# CVTOP.net
KiCad netlist of a schematic drawn in Altium Designer
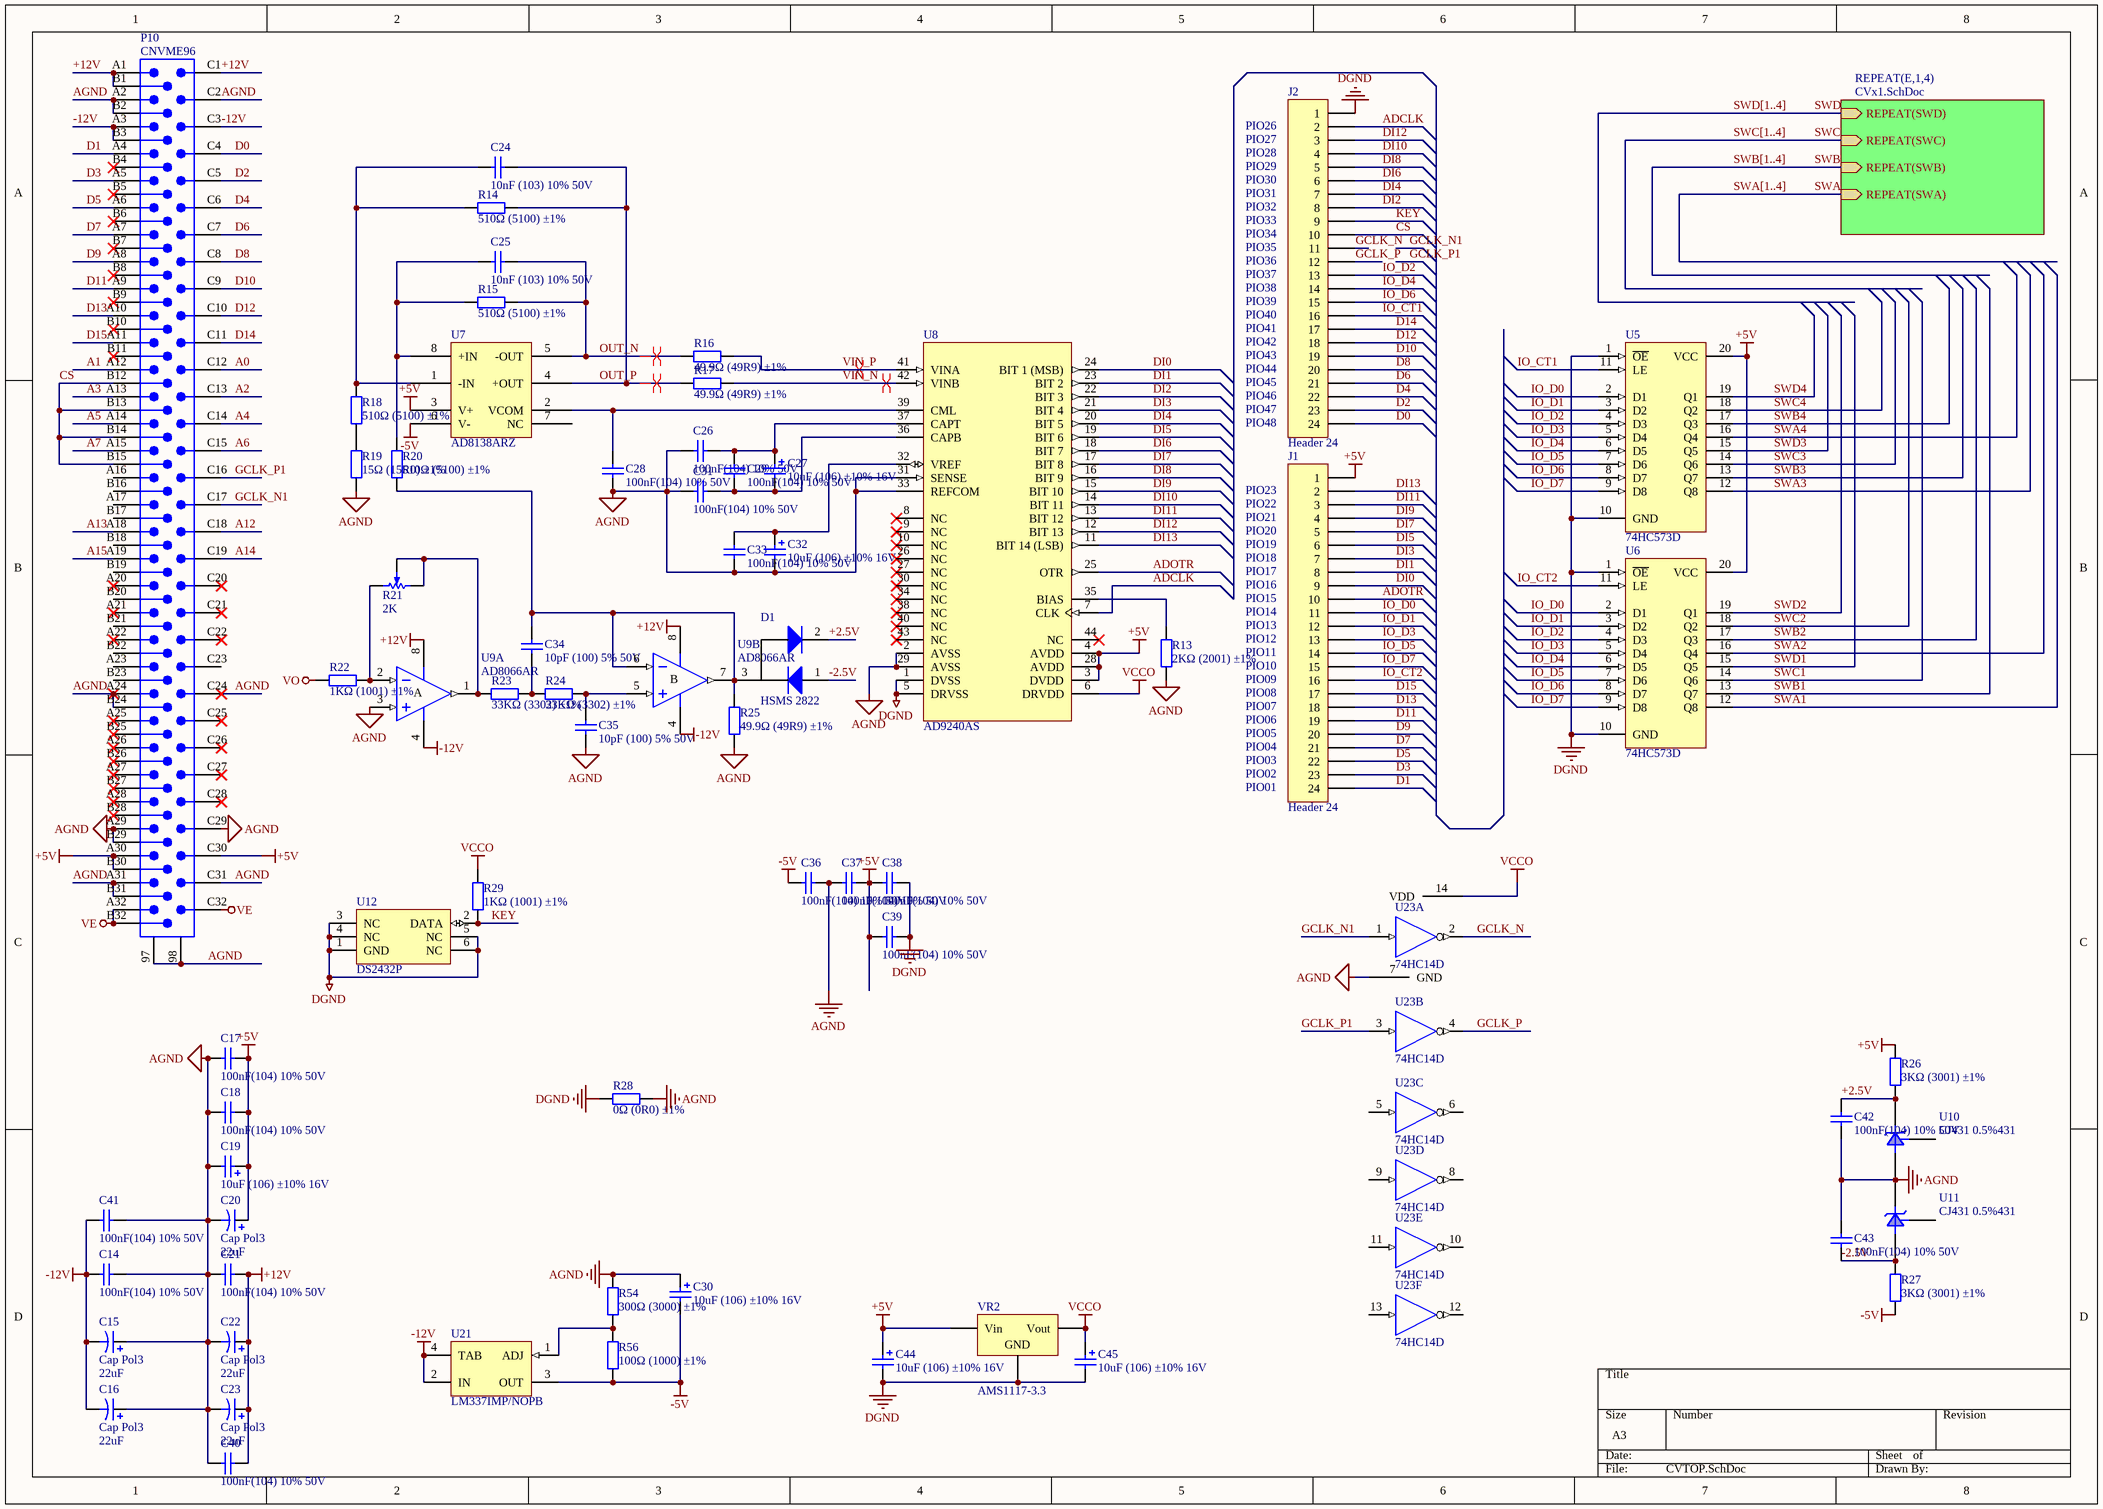
[diagram p0: CVTOP.SchDoc]

(export (version "E")
  (design (tool "Eeschema 10.0.6"))
  (components
    (comp (ref "C14")
      (value "100nF(104) 10% 50V")
      (footprint "LC-0805_C")
      (description "贴片电容")
      (libsource (lib "Miscellaneous Devices LC") (part "0805 100nF(104) 10% 50V"))
    )
    (comp (ref "C15")
      (value "Cap Pol3")
      (footprint "C2225")
      (description "Polarized Capacitor (Surface Mount)")
      (fields (field (name "ALTIUM_VALUE") "22uF") (field (name "PUBLISHER") "Altium Limited"))
      (libsource (lib "Miscellaneous Devices") (part "Cap Pol3"))
    )
    (comp (ref "C16")
      (value "Cap Pol3")
      (footprint "C2225")
      (description "Polarized Capacitor (Surface Mount)")
      (fields (field (name "ALTIUM_VALUE") "22uF") (field (name "PUBLISHER") "Altium Limited"))
      (libsource (lib "Miscellaneous Devices") (part "Cap Pol3"))
    )
    (comp (ref "C17")
      (value "100nF(104) 10% 50V")
      (footprint "LC-0805_C")
      (description "贴片电容")
      (libsource (lib "Miscellaneous Devices LC") (part "0805 100nF(104) 10% 50V"))
    )
    (comp (ref "C18")
      (value "100nF(104) 10% 50V")
      (footprint "LC-0805_C")
      (description "贴片电容")
      (libsource (lib "Miscellaneous Devices LC") (part "0805 100nF(104) 10% 50V"))
    )
    (comp (ref "C19")
      (value "10uF (106) ±10% 16V")
      (footprint "LC-CASE-A_3216")
      (description "钽电容")
      (libsource (lib "Miscellaneous Devices LC") (part "3216 10uF (106) 10% 16V"))
    )
    (comp (ref "C20")
      (value "Cap Pol3")
      (footprint "C2225")
      (description "Polarized Capacitor (Surface Mount)")
      (fields (field (name "ALTIUM_VALUE") "22uF") (field (name "PUBLISHER") "Altium Limited"))
      (libsource (lib "Miscellaneous Devices") (part "Cap Pol3"))
    )
    (comp (ref "C21")
      (value "100nF(104) 10% 50V")
      (footprint "LC-0805_C")
      (description "贴片电容")
      (libsource (lib "Miscellaneous Devices LC") (part "0805 100nF(104) 10% 50V"))
    )
    (comp (ref "C22")
      (value "Cap Pol3")
      (footprint "C2225")
      (description "Polarized Capacitor (Surface Mount)")
      (fields (field (name "ALTIUM_VALUE") "22uF") (field (name "PUBLISHER") "Altium Limited"))
      (libsource (lib "Miscellaneous Devices") (part "Cap Pol3"))
    )
    (comp (ref "C23")
      (value "Cap Pol3")
      (footprint "C2225")
      (description "Polarized Capacitor (Surface Mount)")
      (fields (field (name "ALTIUM_VALUE") "22uF") (field (name "PUBLISHER") "Altium Limited"))
      (libsource (lib "Miscellaneous Devices") (part "Cap Pol3"))
    )
    (comp (ref "C24")
      (value "10nF (103) 10% 50V")
      (footprint "LC-0805_C")
      (description "贴片电容")
      (libsource (lib "Miscellaneous Devices LC") (part "0805 10nF (103) 10% 50V"))
    )
    (comp (ref "C25")
      (value "10nF (103) 10% 50V")
      (footprint "LC-0805_C")
      (description "贴片电容")
      (libsource (lib "Miscellaneous Devices LC") (part "0805 10nF (103) 10% 50V"))
    )
    (comp (ref "C26")
      (value "100nF(104) 10% 50V")
      (footprint "LC-0805_C")
      (description "贴片电容")
      (libsource (lib "Miscellaneous Devices LC") (part "0805 100nF(104) 10% 50V"))
    )
    (comp (ref "C27")
      (value "10uF (106) ±10% 16V")
      (footprint "LC-CASE-A_3216")
      (description "钽电容")
      (libsource (lib "Miscellaneous Devices LC") (part "3216 10uF (106) 10% 16V"))
    )
    (comp (ref "C28")
      (value "100nF(104) 10% 50V")
      (footprint "LC-0805_C")
      (description "贴片电容")
      (libsource (lib "Miscellaneous Devices LC") (part "0805 100nF(104) 10% 50V"))
    )
    (comp (ref "C29")
      (value "100nF(104) 10% 50V")
      (footprint "LC-0805_C")
      (description "贴片电容")
      (libsource (lib "Miscellaneous Devices LC") (part "0805 100nF(104) 10% 50V"))
    )
    (comp (ref "C30")
      (value "10uF (106) ±10% 16V")
      (footprint "LC-CASE-A_3216")
      (description "钽电容")
      (libsource (lib "Miscellaneous Devices LC") (part "3216 10uF (106) 10% 16V"))
    )
    (comp (ref "C31")
      (value "100nF(104) 10% 50V")
      (footprint "LC-0805_C")
      (description "贴片电容")
      (libsource (lib "Miscellaneous Devices LC") (part "0805 100nF(104) 10% 50V"))
    )
    (comp (ref "C32")
      (value "10uF (106) ±10% 16V")
      (footprint "LC-CASE-A_3216")
      (description "钽电容")
      (libsource (lib "Miscellaneous Devices LC") (part "3216 10uF (106) 10% 16V"))
    )
    (comp (ref "C33")
      (value "100nF(104) 10% 50V")
      (footprint "LC-0805_C")
      (description "贴片电容")
      (libsource (lib "Miscellaneous Devices LC") (part "0805 100nF(104) 10% 50V"))
    )
    (comp (ref "C34")
      (value "10pF (100) 5% 50V")
      (footprint "LC-0805_C")
      (description "贴片电容")
      (libsource (lib "Miscellaneous Devices LC") (part "0805 10pF (100) 5% 50V"))
    )
    (comp (ref "C35")
      (value "10pF (100) 5% 50V")
      (footprint "LC-0805_C")
      (description "贴片电容")
      (libsource (lib "Miscellaneous Devices LC") (part "0805 10pF (100) 5% 50V"))
    )
    (comp (ref "C36")
      (value "100nF(104) 10% 50V")
      (footprint "LC-0805_C")
      (description "贴片电容")
      (libsource (lib "Miscellaneous Devices LC") (part "0805 100nF(104) 10% 50V"))
    )
    (comp (ref "C37")
      (value "100nF(104) 10% 50V")
      (footprint "LC-0805_C")
      (description "贴片电容")
      (libsource (lib "Miscellaneous Devices LC") (part "0805 100nF(104) 10% 50V"))
    )
    (comp (ref "C38")
      (value "100nF(104) 10% 50V")
      (footprint "LC-0805_C")
      (description "贴片电容")
      (libsource (lib "Miscellaneous Devices LC") (part "0805 100nF(104) 10% 50V"))
    )
    (comp (ref "C39")
      (value "100nF(104) 10% 50V")
      (footprint "LC-0805_C")
      (description "贴片电容")
      (libsource (lib "Miscellaneous Devices LC") (part "0805 100nF(104) 10% 50V"))
    )
    (comp (ref "C40")
      (value "100nF(104) 10% 50V")
      (footprint "LC-0805_C")
      (description "贴片电容")
      (libsource (lib "Miscellaneous Devices LC") (part "0805 100nF(104) 10% 50V"))
    )
    (comp (ref "C41")
      (value "100nF(104) 10% 50V")
      (footprint "LC-0805_C")
      (description "贴片电容")
      (libsource (lib "Miscellaneous Devices LC") (part "0805 100nF(104) 10% 50V"))
    )
    (comp (ref "C42")
      (value "100nF(104) 10% 50V")
      (footprint "LC-0805_C")
      (description "贴片电容")
      (libsource (lib "Miscellaneous Devices LC") (part "0805 100nF(104) 10% 50V"))
    )
    (comp (ref "C43")
      (value "100nF(104) 10% 50V")
      (footprint "LC-0805_C")
      (description "贴片电容")
      (libsource (lib "Miscellaneous Devices LC") (part "0805 100nF(104) 10% 50V"))
    )
    (comp (ref "C44")
      (value "10uF (106) ±10% 16V")
      (footprint "LC-CASE-A_3216")
      (description "钽电容")
      (libsource (lib "Miscellaneous Devices LC") (part "3216 10uF (106) 10% 16V"))
    )
    (comp (ref "C45")
      (value "10uF (106) ±10% 16V")
      (footprint "LC-CASE-A_3216")
      (description "钽电容")
      (libsource (lib "Miscellaneous Devices LC") (part "3216 10uF (106) 10% 16V"))
    )
    (comp (ref "D1")
      (value "HSMS 2822")
      (footprint "LC-SOT-23(SOT-23-3)")
      (description "开关二极管")
      (libsource (lib "Miscellaneous Devices LC") (part "SOT-23 BAV99 A7W"))
    )
    (comp (ref "J1")
      (value "Header 24")
      (footprint "HDR1X24")
      (description "Header, 24-Pin")
      (fields (field (name "PUBLISHER") "Altium Limited"))
      (libsource (lib "Miscellaneous Connectors") (part "Header 24"))
    )
    (comp (ref "J2")
      (value "Header 24")
      (footprint "HDR1X24")
      (description "Header, 24-Pin")
      (fields (field (name "PUBLISHER") "Altium Limited"))
      (libsource (lib "Miscellaneous Connectors") (part "Header 24"))
    )
    (comp (ref "P10")
      (value "CNVME96")
      (footprint "CNVME96")
      (description "96-Pin Connector (3x32 2.54mm grid)")
      (libsource (lib "*") (part "CNVME96"))
    )
    (comp (ref "R13")
      (value "2KΩ (2001) ±1%")
      (footprint "LC-0805_R")
      (description "贴片电阻")
      (libsource (lib "Miscellaneous Devices LC") (part "0805 2KΩ (2001) 1%"))
    )
    (comp (ref "R14")
      (value "510Ω (5100) ±1%")
      (footprint "LC-0805_R")
      (description "贴片电阻")
      (libsource (lib "") (part "0805 510Ω (5100) 1%_1"))
    )
    (comp (ref "R15")
      (value "510Ω (5100) ±1%")
      (footprint "LC-0805_R")
      (description "贴片电阻")
      (libsource (lib "") (part "0805 510Ω (5100) 1%_1"))
    )
    (comp (ref "R16")
      (value "49.9Ω (49R9) ±1%")
      (footprint "LC-0805_R")
      (description "贴片电阻")
      (libsource (lib "") (part "0805 49.9Ω (49R9) 1%_1"))
    )
    (comp (ref "R17")
      (value "49.9Ω (49R9) ±1%")
      (footprint "LC-0805_R")
      (description "贴片电阻")
      (libsource (lib "") (part "0805 49.9Ω (49R9) 1%_1"))
    )
    (comp (ref "R18")
      (value "510Ω (5100) ±1%")
      (footprint "LC-0805_R")
      (description "贴片电阻")
      (libsource (lib "Miscellaneous Devices LC") (part "0805 510Ω (5100) 1%"))
    )
    (comp (ref "R19")
      (value "15Ω (15R0) ±1%")
      (footprint "LC-0805_R")
      (description "贴片电阻")
      (libsource (lib "Miscellaneous Devices LC") (part "0805 15Ω (15R0) 1%"))
    )
    (comp (ref "R20")
      (value "510Ω (5100) ±1%")
      (footprint "LC-0805_R")
      (description "贴片电阻")
      (libsource (lib "Miscellaneous Devices LC") (part "0805 510Ω (5100) 1%"))
    )
    (comp (ref "R21")
      (value "2K")
      (footprint "POT4MM-2")
      (description "Square Trimming Potentiometer")
      (fields (field (name "PUBLISHER") "Altium Limited"))
      (libsource (lib "Miscellaneous Devices") (part "RPot SM"))
    )
    (comp (ref "R22")
      (value "1KΩ (1001) ±1%")
      (footprint "LC-0805_R")
      (description "贴片电阻")
      (libsource (lib "Miscellaneous Devices LC") (part "0805 1KΩ (1001) 1%"))
    )
    (comp (ref "R23")
      (value "33KΩ (3302) ±1%")
      (footprint "LC-0805_R")
      (description "贴片电阻")
      (libsource (lib "Miscellaneous Devices LC") (part "0805 33KΩ (3302) 1%"))
    )
    (comp (ref "R24")
      (value "33KΩ (3302) ±1%")
      (footprint "LC-0805_R")
      (description "贴片电阻")
      (libsource (lib "Miscellaneous Devices LC") (part "0805 33KΩ (3302) 1%"))
    )
    (comp (ref "R25")
      (value "49.9Ω (49R9) ±1%")
      (footprint "LC-0805_R")
      (description "贴片电阻")
      (libsource (lib "Miscellaneous Devices LC") (part "0805 49.9Ω (49R9) 1%"))
    )
    (comp (ref "R26")
      (value "3KΩ (3001) ±1%")
      (footprint "LC-0805_R")
      (description "贴片电阻")
      (libsource (lib "Miscellaneous Devices LC") (part "0805 3KΩ (3001) 1%"))
    )
    (comp (ref "R27")
      (value "3KΩ (3001) ±1%")
      (footprint "LC-0805_R")
      (description "贴片电阻")
      (libsource (lib "Miscellaneous Devices LC") (part "0805 3KΩ (3001) 1%"))
    )
    (comp (ref "R28")
      (value "0Ω (0R0) ±1%")
      (footprint "LC-0805_R")
      (description "贴片电阻")
      (libsource (lib "Miscellaneous Devices LC") (part "0805 0Ω (0R0) 1%"))
    )
    (comp (ref "R29")
      (value "1KΩ (1001) ±1%")
      (footprint "LC-0805_R")
      (description "贴片电阻")
      (libsource (lib "") (part "0805 1KΩ (1001) 1%_1"))
    )
    (comp (ref "R54")
      (value "300Ω (3000) ±1%")
      (footprint "LC-0805_R")
      (description "贴片电阻")
      (libsource (lib "Miscellaneous Devices LC") (part "0805 300Ω (3000) 1%"))
    )
    (comp (ref "R56")
      (value "100Ω (1000) ±1%")
      (footprint "LC-0805_R")
      (description "贴片电阻")
      (libsource (lib "Miscellaneous Devices LC") (part "0805 100Ω (1000) 1%"))
    )
    (comp (ref "U5")
      (value "74HC573D")
      (footprint "LC-SOIC-20_300mil")
      (description "74系列逻辑芯片")
      (libsource (lib "Miscellaneous Devices LC") (part "74HC573D"))
    )
    (comp (ref "U6")
      (value "74HC573D")
      (footprint "LC-SOIC-20_300mil")
      (description "74系列逻辑芯片")
      (libsource (lib "Miscellaneous Devices LC") (part "74HC573D"))
    )
    (comp (ref "U7") (value "AD8138ARZ") (footprint "SO-8_N") (libsource (lib "AD8138") (part "AD8138ARZ")))
    (comp (ref "U8")
      (value "AD9240AS")
      (footprint "S-44-MQFP_N")
      (description "Complete 14-Bit, 10 MSPS Monolithic A/D Converter, 44-Pin MQFP, Industrial")
      (fields (field (name "PUBLISHER") "Altium Limited"))
      (libsource (lib "AD Converter Analog to Digital") (part "AD9240AS"))
    )
    (comp (ref "U9")
      (value "AD8066AR")
      (footprint "mini-ET:SO-8_N")
      (description "Low Cost, 300MHz Voltage Feedback Amplifier")
      (fields (field (name "PUBLISHER") "Altium Limited"))
      (libsource (lib "AD Operational Amplifier") (part "AD8056AR"))
    )
    (comp (ref "U10")
      (value "CJ431 0.5%431")
      (footprint "LC-SOT-23(SOT-23-3)")
      (description "电压基准")
      (libsource (lib "Miscellaneous Devices LC") (part "CJ431 0.5%431"))
    )
    (comp (ref "U11")
      (value "CJ431 0.5%431")
      (footprint "LC-SOT-23(SOT-23-3)")
      (description "电压基准")
      (libsource (lib "Miscellaneous Devices LC") (part "CJ431 0.5%431"))
    )
    (comp (ref "U12")
      (value "DS2432P")
      (footprint "TSOC6")
      (description "256-Bit 1-Wire EEPROM")
      (fields (field (name "PUBLISHER") "Altium Limited"))
      (libsource (lib "Dallas Memory EEPROM") (part "DS2430AP"))
    )
    (comp (ref "U21")
      (value "LM337IMP/NOPB")
      (footprint "MP04A_N")
      (description "3-Terminal Adjustable Negative Regulator, 4-pin SOT-223, Pb-Free")
      (fields
        (field (name "MANUFACTURER") "National Semiconductor")
        (field (name "PUBLISHER") "Altium Limited")
      )
      (libsource (lib "NSC LDO") (part "LM337IMP/NOPB"))
    )
    (comp (ref "U23")
      (value "74HC14D")
      (footprint "LC-SOIC-14_150mil")
      (description "74系列逻辑芯片")
      (libsource (lib "Miscellaneous Devices LC") (part "74HC14D_[C5605]"))
    )
    (comp (ref "VR2")
      (value "AMS1117-3.3")
      (footprint "LC-SOT-223")
      (description "低压差线性稳压(LDO)")
      (libsource (lib "Miscellaneous Devices LC") (part "SOT-223 AMS1117-3.3"))
    )
  )
  (nets
    (net (code "1") (name "+5V") (class "Default")
      (node (ref "C17") (pin "2") (pinfunction "2_2") (pintype "passive"))
      (node (ref "C18") (pin "2") (pinfunction "2_2") (pintype "passive"))
      (node (ref "C19") (pin "1") (pinfunction "1_1") (pintype "passive"))
      (node (ref "C20") (pin "1") (pinfunction "1_1") (pintype "passive"))
      (node (ref "C37") (pin "1") (pinfunction "1_1") (pintype "passive"))
      (node (ref "C38") (pin "2") (pinfunction "2_2") (pintype "passive"))
      (node (ref "C39") (pin "2") (pinfunction "2_2") (pintype "passive"))
      (node (ref "C44") (pin "1") (pinfunction "1_1") (pintype "passive"))
      (node (ref "J1") (pin "1") (pinfunction "1_1") (pintype "passive"))
      (node (ref "P10") (pin "A30") (pinfunction "A30_A30") (pintype "passive"))
      (node (ref "P10") (pin "B30") (pinfunction "B30_B30") (pintype "passive"))
      (node (ref "P10") (pin "C30") (pinfunction "C30_C30") (pintype "passive"))
      (node (ref "R26") (pin "2") (pinfunction "2_2") (pintype "passive"))
      (node (ref "U5") (pin "20") (pinfunction "VCC_20") (pintype "power_in"))
      (node (ref "U6") (pin "20") (pinfunction "VCC_20") (pintype "power_in"))
      (node (ref "U7") (pin "3") (pinfunction "V+_3") (pintype "passive"))
      (node (ref "U8") (pin "28") (pinfunction "AVDD_28") (pintype "power_in"))
      (node (ref "U8") (pin "3") (pinfunction "DVDD_3") (pintype "power_in"))
      (node (ref "U8") (pin "4") (pinfunction "AVDD_4") (pintype "power_in"))
      (node (ref "VR2") (pin "3") (pinfunction "Vin_3") (pintype "passive"))
    )
    (net (code "2") (name "+12V") (class "Default")
      (node (ref "C21") (pin "2") (pinfunction "2_2") (pintype "passive"))
      (node (ref "C22") (pin "1") (pinfunction "1_1") (pintype "passive"))
      (node (ref "C23") (pin "1") (pinfunction "1_1") (pintype "passive"))
      (node (ref "C40") (pin "1") (pinfunction "1_1") (pintype "passive"))
      (node (ref "P10") (pin "A1") (pinfunction "A1_A1") (pintype "passive"))
      (node (ref "P10") (pin "B1") (pinfunction "B1_B1") (pintype "passive"))
      (node (ref "P10") (pin "C1") (pinfunction "C1_C1") (pintype "passive"))
      (node (ref "U9") (pin "8") (pinfunction "V+_8") (pintype "power_in"))
    )
    (net (code "3") (name "-5V") (class "Default")
      (node (ref "C30") (pin "2") (pinfunction "2_2") (pintype "passive"))
      (node (ref "C36") (pin "2") (pinfunction "2_2") (pintype "passive"))
      (node (ref "R27") (pin "1") (pinfunction "1_1") (pintype "passive"))
      (node (ref "R56") (pin "1") (pinfunction "1_1") (pintype "passive"))
      (node (ref "U21") (pin "3") (pinfunction "OUT_3") (pintype "power_in"))
      (node (ref "U7") (pin "6") (pinfunction "V-_6") (pintype "passive"))
    )
    (net (code "4") (name "-12V") (class "Default")
      (node (ref "C14") (pin "1") (pinfunction "1_1") (pintype "passive"))
      (node (ref "C15") (pin "2") (pinfunction "2_2") (pintype "passive"))
      (node (ref "C16") (pin "2") (pinfunction "2_2") (pintype "passive"))
      (node (ref "C41") (pin "2") (pinfunction "2_2") (pintype "passive"))
      (node (ref "P10") (pin "A3") (pinfunction "A3_A3") (pintype "passive"))
      (node (ref "P10") (pin "B3") (pinfunction "B3_B3") (pintype "passive"))
      (node (ref "P10") (pin "C3") (pinfunction "C3_C3") (pintype "passive"))
      (node (ref "U21") (pin "2") (pinfunction "IN_2") (pintype "power_in"))
      (node (ref "U21") (pin "4") (pinfunction "TAB_4") (pintype "power_in"))
      (node (ref "U9") (pin "4") (pinfunction "V-_4") (pintype "power_in"))
    )
    (net (code "5") (name "/+2.5V") (class "Default")
      (node (ref "C42") (pin "1") (pinfunction "1_1") (pintype "passive"))
      (node (ref "D1") (pin "2") (pinfunction "A_2") (pintype "passive"))
      (node (ref "R26") (pin "1") (pinfunction "1_1") (pintype "passive"))
      (node (ref "U10") (pin "2") (pinfunction "K_2") (pintype "passive"))
    )
    (net (code "6") (name "/-2.5V") (class "Default")
      (node (ref "C43") (pin "2") (pinfunction "2_2") (pintype "passive"))
      (node (ref "D1") (pin "1") (pinfunction "A_1") (pintype "passive"))
      (node (ref "R27") (pin "2") (pinfunction "2_2") (pintype "passive"))
      (node (ref "U11") (pin "3") (pinfunction "A_3") (pintype "passive"))
    )
    (net (code "7") (name "/A0") (class "Default")
      (node (ref "P10") (pin "C12") (pinfunction "C12_C12") (pintype "passive"))
    )
    (net (code "8") (name "/A1") (class "Default")
      (node (ref "P10") (pin "A12") (pinfunction "A12_A12") (pintype "passive"))
    )
    (net (code "9") (name "/A2") (class "Default")
      (node (ref "P10") (pin "C13") (pinfunction "C13_C13") (pintype "passive"))
    )
    (net (code "10") (name "/A3") (class "Default")
      (node (ref "P10") (pin "A13") (pinfunction "A13_A13") (pintype "passive"))
    )
    (net (code "11") (name "/A4") (class "Default")
      (node (ref "P10") (pin "C14") (pinfunction "C14_C14") (pintype "passive"))
    )
    (net (code "12") (name "/A5") (class "Default")
      (node (ref "P10") (pin "A14") (pinfunction "A14_A14") (pintype "passive"))
    )
    (net (code "13") (name "/A6") (class "Default")
      (node (ref "P10") (pin "C15") (pinfunction "C15_C15") (pintype "passive"))
    )
    (net (code "14") (name "/A7") (class "Default")
      (node (ref "P10") (pin "A15") (pinfunction "A15_A15") (pintype "passive"))
    )
    (net (code "15") (name "/A12") (class "Default")
      (node (ref "P10") (pin "C18") (pinfunction "C18_C18") (pintype "passive"))
    )
    (net (code "16") (name "/A13") (class "Default")
      (node (ref "P10") (pin "A18") (pinfunction "A18_A18") (pintype "passive"))
    )
    (net (code "17") (name "/A14") (class "Default")
      (node (ref "P10") (pin "C19") (pinfunction "C19_C19") (pintype "passive"))
    )
    (net (code "18") (name "/A15") (class "Default")
      (node (ref "P10") (pin "A19") (pinfunction "A19_A19") (pintype "passive"))
    )
    (net (code "19") (name "/ADCLK") (class "Default")
      (node (ref "J2") (pin "2") (pinfunction "2_2") (pintype "passive"))
      (node (ref "U8") (pin "7") (pinfunction "CLK_7") (pintype "input"))
    )
    (net (code "20") (name "/ADOTR") (class "Default")
      (node (ref "J1") (pin "10") (pinfunction "10_10") (pintype "passive"))
      (node (ref "U8") (pin "25") (pinfunction "OTR_25") (pintype "output"))
    )
    (net (code "21") (name "/CS") (class "Default")
      (node (ref "J2") (pin "10") (pinfunction "10_10") (pintype "passive"))
      (node (ref "P10") (pin "B12") (pinfunction "B12_B12") (pintype "passive"))
      (node (ref "P10") (pin "B13") (pinfunction "B13_B13") (pintype "passive"))
      (node (ref "P10") (pin "B14") (pinfunction "B14_B14") (pintype "passive"))
      (node (ref "P10") (pin "B15") (pinfunction "B15_B15") (pintype "passive"))
    )
    (net (code "22") (name "/D0") (class "Default")
      (node (ref "J2") (pin "24") (pinfunction "24_24") (pintype "passive"))
      (node (ref "P10") (pin "C4") (pinfunction "C4_C4") (pintype "passive"))
    )
    (net (code "23") (name "/D1") (class "Default")
      (node (ref "J1") (pin "24") (pinfunction "24_24") (pintype "passive"))
      (node (ref "P10") (pin "A4") (pinfunction "A4_A4") (pintype "passive"))
    )
    (net (code "24") (name "/D2") (class "Default")
      (node (ref "J2") (pin "23") (pinfunction "23_23") (pintype "passive"))
      (node (ref "P10") (pin "C5") (pinfunction "C5_C5") (pintype "passive"))
    )
    (net (code "25") (name "/D3") (class "Default")
      (node (ref "J1") (pin "23") (pinfunction "23_23") (pintype "passive"))
      (node (ref "P10") (pin "A5") (pinfunction "A5_A5") (pintype "passive"))
    )
    (net (code "26") (name "/D4") (class "Default")
      (node (ref "J2") (pin "22") (pinfunction "22_22") (pintype "passive"))
      (node (ref "P10") (pin "C6") (pinfunction "C6_C6") (pintype "passive"))
    )
    (net (code "27") (name "/D5") (class "Default")
      (node (ref "J1") (pin "22") (pinfunction "22_22") (pintype "passive"))
      (node (ref "P10") (pin "A6") (pinfunction "A6_A6") (pintype "passive"))
    )
    (net (code "28") (name "/D6") (class "Default")
      (node (ref "J2") (pin "21") (pinfunction "21_21") (pintype "passive"))
      (node (ref "P10") (pin "C7") (pinfunction "C7_C7") (pintype "passive"))
    )
    (net (code "29") (name "/D7") (class "Default")
      (node (ref "J1") (pin "21") (pinfunction "21_21") (pintype "passive"))
      (node (ref "P10") (pin "A7") (pinfunction "A7_A7") (pintype "passive"))
    )
    (net (code "30") (name "/D8") (class "Default")
      (node (ref "J2") (pin "20") (pinfunction "20_20") (pintype "passive"))
      (node (ref "P10") (pin "C8") (pinfunction "C8_C8") (pintype "passive"))
    )
    (net (code "31") (name "/D9") (class "Default")
      (node (ref "J1") (pin "20") (pinfunction "20_20") (pintype "passive"))
      (node (ref "P10") (pin "A8") (pinfunction "A8_A8") (pintype "passive"))
    )
    (net (code "32") (name "/D10") (class "Default")
      (node (ref "J2") (pin "19") (pinfunction "19_19") (pintype "passive"))
      (node (ref "P10") (pin "C9") (pinfunction "C9_C9") (pintype "passive"))
    )
    (net (code "33") (name "/D11") (class "Default")
      (node (ref "J1") (pin "19") (pinfunction "19_19") (pintype "passive"))
      (node (ref "P10") (pin "A9") (pinfunction "A9_A9") (pintype "passive"))
    )
    (net (code "34") (name "/D12") (class "Default")
      (node (ref "J2") (pin "18") (pinfunction "18_18") (pintype "passive"))
      (node (ref "P10") (pin "C10") (pinfunction "C10_C10") (pintype "passive"))
    )
    (net (code "35") (name "/D13") (class "Default")
      (node (ref "J1") (pin "18") (pinfunction "18_18") (pintype "passive"))
      (node (ref "P10") (pin "A10") (pinfunction "A10_A10") (pintype "passive"))
    )
    (net (code "36") (name "/D14") (class "Default")
      (node (ref "J2") (pin "17") (pinfunction "17_17") (pintype "passive"))
      (node (ref "P10") (pin "C11") (pinfunction "C11_C11") (pintype "passive"))
    )
    (net (code "37") (name "/D15") (class "Default")
      (node (ref "J1") (pin "17") (pinfunction "17_17") (pintype "passive"))
      (node (ref "P10") (pin "A11") (pinfunction "A11_A11") (pintype "passive"))
    )
    (net (code "38") (name "/DI0") (class "Default")
      (node (ref "J1") (pin "9") (pinfunction "9_9") (pintype "passive"))
      (node (ref "U8") (pin "24") (pinfunction "BIT_1_(MSB)_24") (pintype "output"))
    )
    (net (code "39") (name "/DI1") (class "Default")
      (node (ref "J1") (pin "8") (pinfunction "8_8") (pintype "passive"))
      (node (ref "U8") (pin "23") (pinfunction "BIT_2_23") (pintype "output"))
    )
    (net (code "40") (name "/DI2") (class "Default")
      (node (ref "J2") (pin "8") (pinfunction "8_8") (pintype "passive"))
      (node (ref "U8") (pin "22") (pinfunction "BIT_3_22") (pintype "output"))
    )
    (net (code "41") (name "/DI3") (class "Default")
      (node (ref "J1") (pin "7") (pinfunction "7_7") (pintype "passive"))
      (node (ref "U8") (pin "21") (pinfunction "BIT_4_21") (pintype "output"))
    )
    (net (code "42") (name "/DI4") (class "Default")
      (node (ref "J2") (pin "7") (pinfunction "7_7") (pintype "passive"))
      (node (ref "U8") (pin "20") (pinfunction "BIT_5_20") (pintype "output"))
    )
    (net (code "43") (name "/DI5") (class "Default")
      (node (ref "J1") (pin "6") (pinfunction "6_6") (pintype "passive"))
      (node (ref "U8") (pin "19") (pinfunction "BIT_6_19") (pintype "output"))
    )
    (net (code "44") (name "/DI6") (class "Default")
      (node (ref "J2") (pin "6") (pinfunction "6_6") (pintype "passive"))
      (node (ref "U8") (pin "18") (pinfunction "BIT_7_18") (pintype "output"))
    )
    (net (code "45") (name "/DI7") (class "Default")
      (node (ref "J1") (pin "5") (pinfunction "5_5") (pintype "passive"))
      (node (ref "U8") (pin "17") (pinfunction "BIT_8_17") (pintype "output"))
    )
    (net (code "46") (name "/DI8") (class "Default")
      (node (ref "J2") (pin "5") (pinfunction "5_5") (pintype "passive"))
      (node (ref "U8") (pin "16") (pinfunction "BIT_9_16") (pintype "output"))
    )
    (net (code "47") (name "/DI9") (class "Default")
      (node (ref "J1") (pin "4") (pinfunction "4_4") (pintype "passive"))
      (node (ref "U8") (pin "15") (pinfunction "BIT_10_15") (pintype "output"))
    )
    (net (code "48") (name "/DI10") (class "Default")
      (node (ref "J2") (pin "4") (pinfunction "4_4") (pintype "passive"))
      (node (ref "U8") (pin "14") (pinfunction "BIT_11_14") (pintype "output"))
    )
    (net (code "49") (name "/DI11") (class "Default")
      (node (ref "J1") (pin "3") (pinfunction "3_3") (pintype "passive"))
      (node (ref "U8") (pin "13") (pinfunction "BIT_12_13") (pintype "output"))
    )
    (net (code "50") (name "/DI12") (class "Default")
      (node (ref "J2") (pin "3") (pinfunction "3_3") (pintype "passive"))
      (node (ref "U8") (pin "12") (pinfunction "BIT_13_12") (pintype "output"))
    )
    (net (code "51") (name "/DI13") (class "Default")
      (node (ref "J1") (pin "2") (pinfunction "2_2") (pintype "passive"))
      (node (ref "U8") (pin "11") (pinfunction "BIT_14_(LSB)_11") (pintype "output"))
    )
    (net (code "52") (name "/GCLK_N") (class "Default")
      (node (ref "J2") (pin "11") (pinfunction "11_11") (pintype "passive"))
      (node (ref "U23") (pin "2") (pinfunction "Y_2") (pintype "output"))
    )
    (net (code "53") (name "/GCLK_N1") (class "Default")
      (node (ref "P10") (pin "C17") (pinfunction "C17_C17") (pintype "passive"))
      (node (ref "U23") (pin "1") (pinfunction "A_1") (pintype "input"))
    )
    (net (code "54") (name "/GCLK_P") (class "Default")
      (node (ref "J2") (pin "12") (pinfunction "12_12") (pintype "passive"))
      (node (ref "U23") (pin "4") (pinfunction "Y_4") (pintype "output"))
    )
    (net (code "55") (name "/GCLK_P1") (class "Default")
      (node (ref "P10") (pin "C16") (pinfunction "C16_C16") (pintype "passive"))
      (node (ref "U23") (pin "3") (pinfunction "A_3") (pintype "input"))
    )
    (net (code "56") (name "/IO_CT1") (class "Default")
      (node (ref "J2") (pin "16") (pinfunction "16_16") (pintype "passive"))
      (node (ref "U5") (pin "11") (pinfunction "LE_11") (pintype "input"))
    )
    (net (code "57") (name "/IO_CT2") (class "Default")
      (node (ref "J1") (pin "16") (pinfunction "16_16") (pintype "passive"))
      (node (ref "U6") (pin "11") (pinfunction "LE_11") (pintype "input"))
    )
    (net (code "58") (name "/IO_D0") (class "Default")
      (node (ref "J1") (pin "11") (pinfunction "11_11") (pintype "passive"))
      (node (ref "U5") (pin "2") (pinfunction "D1_2") (pintype "input"))
      (node (ref "U6") (pin "2") (pinfunction "D1_2") (pintype "input"))
    )
    (net (code "59") (name "/IO_D1") (class "Default")
      (node (ref "J1") (pin "12") (pinfunction "12_12") (pintype "passive"))
      (node (ref "U5") (pin "3") (pinfunction "D2_3") (pintype "input"))
      (node (ref "U6") (pin "3") (pinfunction "D2_3") (pintype "input"))
    )
    (net (code "60") (name "/IO_D2") (class "Default")
      (node (ref "J2") (pin "13") (pinfunction "13_13") (pintype "passive"))
      (node (ref "U5") (pin "4") (pinfunction "D3_4") (pintype "input"))
      (node (ref "U6") (pin "4") (pinfunction "D3_4") (pintype "input"))
    )
    (net (code "61") (name "/IO_D3") (class "Default")
      (node (ref "J1") (pin "13") (pinfunction "13_13") (pintype "passive"))
      (node (ref "U5") (pin "5") (pinfunction "D4_5") (pintype "input"))
      (node (ref "U6") (pin "5") (pinfunction "D4_5") (pintype "input"))
    )
    (net (code "62") (name "/IO_D4") (class "Default")
      (node (ref "J2") (pin "14") (pinfunction "14_14") (pintype "passive"))
      (node (ref "U5") (pin "6") (pinfunction "D5_6") (pintype "input"))
      (node (ref "U6") (pin "6") (pinfunction "D5_6") (pintype "input"))
    )
    (net (code "63") (name "/IO_D5") (class "Default")
      (node (ref "J1") (pin "14") (pinfunction "14_14") (pintype "passive"))
      (node (ref "U5") (pin "7") (pinfunction "D6_7") (pintype "input"))
      (node (ref "U6") (pin "7") (pinfunction "D6_7") (pintype "input"))
    )
    (net (code "64") (name "/IO_D6") (class "Default")
      (node (ref "J2") (pin "15") (pinfunction "15_15") (pintype "passive"))
      (node (ref "U5") (pin "8") (pinfunction "D7_8") (pintype "input"))
      (node (ref "U6") (pin "8") (pinfunction "D7_8") (pintype "input"))
    )
    (net (code "65") (name "/IO_D7") (class "Default")
      (node (ref "J1") (pin "15") (pinfunction "15_15") (pintype "passive"))
      (node (ref "U5") (pin "9") (pinfunction "D8_9") (pintype "input"))
      (node (ref "U6") (pin "9") (pinfunction "D8_9") (pintype "input"))
    )
    (net (code "66") (name "/KEY") (class "Default")
      (node (ref "J2") (pin "9") (pinfunction "9_9") (pintype "passive"))
      (node (ref "R29") (pin "1") (pinfunction "1_1") (pintype "passive"))
      (node (ref "U12") (pin "2") (pinfunction "DATA_2") (pintype "bidirectional"))
    )
    (net (code "67") (name "/OUT_N") (class "Default")
      (node (ref "C25") (pin "2") (pinfunction "2_2") (pintype "passive"))
      (node (ref "R15") (pin "2") (pinfunction "2_2") (pintype "passive"))
      (node (ref "R16") (pin "1") (pinfunction "1_1") (pintype "passive"))
      (node (ref "U7") (pin "5") (pinfunction "-OUT_5") (pintype "passive"))
    )
    (net (code "68") (name "/OUT_P") (class "Default")
      (node (ref "C24") (pin "2") (pinfunction "2_2") (pintype "passive"))
      (node (ref "R14") (pin "2") (pinfunction "2_2") (pintype "passive"))
      (node (ref "R17") (pin "1") (pinfunction "1_1") (pintype "passive"))
      (node (ref "U7") (pin "4") (pinfunction "+OUT_4") (pintype "passive"))
    )
    (net (code "70") (name "/SWA1") (class "Default")
      (node (ref "U6") (pin "12") (pinfunction "Q8_12") (pintype "tri_state"))
    )
    (net (code "71") (name "/SWA2") (class "Default")
      (node (ref "U6") (pin "16") (pinfunction "Q4_16") (pintype "tri_state"))
    )
    (net (code "72") (name "/SWA3") (class "Default")
      (node (ref "U5") (pin "12") (pinfunction "Q8_12") (pintype "tri_state"))
    )
    (net (code "73") (name "/SWA4") (class "Default")
      (node (ref "U5") (pin "16") (pinfunction "Q4_16") (pintype "tri_state"))
    )
    (net (code "76") (name "/SWB1") (class "Default")
      (node (ref "U6") (pin "13") (pinfunction "Q7_13") (pintype "tri_state"))
    )
    (net (code "77") (name "/SWB2") (class "Default")
      (node (ref "U6") (pin "17") (pinfunction "Q3_17") (pintype "tri_state"))
    )
    (net (code "78") (name "/SWB3") (class "Default")
      (node (ref "U5") (pin "13") (pinfunction "Q7_13") (pintype "tri_state"))
    )
    (net (code "79") (name "/SWB4") (class "Default")
      (node (ref "U5") (pin "17") (pinfunction "Q3_17") (pintype "tri_state"))
    )
    (net (code "82") (name "/SWC1") (class "Default")
      (node (ref "U6") (pin "14") (pinfunction "Q6_14") (pintype "tri_state"))
    )
    (net (code "83") (name "/SWC2") (class "Default")
      (node (ref "U6") (pin "18") (pinfunction "Q2_18") (pintype "tri_state"))
    )
    (net (code "84") (name "/SWC3") (class "Default")
      (node (ref "U5") (pin "14") (pinfunction "Q6_14") (pintype "tri_state"))
    )
    (net (code "85") (name "/SWC4") (class "Default")
      (node (ref "U5") (pin "18") (pinfunction "Q2_18") (pintype "tri_state"))
    )
    (net (code "88") (name "/SWD1") (class "Default")
      (node (ref "U6") (pin "15") (pinfunction "Q5_15") (pintype "tri_state"))
    )
    (net (code "89") (name "/SWD2") (class "Default")
      (node (ref "U6") (pin "19") (pinfunction "Q1_19") (pintype "tri_state"))
    )
    (net (code "90") (name "/SWD3") (class "Default")
      (node (ref "U5") (pin "15") (pinfunction "Q5_15") (pintype "tri_state"))
    )
    (net (code "91") (name "/SWD4") (class "Default")
      (node (ref "U5") (pin "19") (pinfunction "Q1_19") (pintype "tri_state"))
    )
    (net (code "93") (name "/VIN_N") (class "Default")
      (node (ref "R17") (pin "2") (pinfunction "2_2") (pintype "passive"))
      (node (ref "U8") (pin "42") (pinfunction "VINB_42") (pintype "input"))
    )
    (net (code "94") (name "/VIN_P") (class "Default")
      (node (ref "R16") (pin "2") (pinfunction "2_2") (pintype "passive"))
      (node (ref "U8") (pin "41") (pinfunction "VINA_41") (pintype "input"))
    )
    (net (code "95") (name "AGND") (class "Default")
      (node (ref "C14") (pin "2") (pinfunction "2_2") (pintype "passive"))
      (node (ref "C15") (pin "1") (pinfunction "1_1") (pintype "passive"))
      (node (ref "C16") (pin "1") (pinfunction "1_1") (pintype "passive"))
      (node (ref "C17") (pin "1") (pinfunction "1_1") (pintype "passive"))
      (node (ref "C18") (pin "1") (pinfunction "1_1") (pintype "passive"))
      (node (ref "C19") (pin "2") (pinfunction "2_2") (pintype "passive"))
      (node (ref "C20") (pin "2") (pinfunction "2_2") (pintype "passive"))
      (node (ref "C21") (pin "1") (pinfunction "1_1") (pintype "passive"))
      (node (ref "C22") (pin "2") (pinfunction "2_2") (pintype "passive"))
      (node (ref "C23") (pin "2") (pinfunction "2_2") (pintype "passive"))
      (node (ref "C26") (pin "2") (pinfunction "2_2") (pintype "passive"))
      (node (ref "C28") (pin "1") (pinfunction "1_1") (pintype "passive"))
      (node (ref "C30") (pin "1") (pinfunction "1_1") (pintype "passive"))
      (node (ref "C31") (pin "2") (pinfunction "2_2") (pintype "passive"))
      (node (ref "C32") (pin "2") (pinfunction "2_2") (pintype "passive"))
      (node (ref "C33") (pin "1") (pinfunction "1_1") (pintype "passive"))
      (node (ref "C35") (pin "1") (pinfunction "1_1") (pintype "passive"))
      (node (ref "C36") (pin "1") (pinfunction "1_1") (pintype "passive"))
      (node (ref "C37") (pin "2") (pinfunction "2_2") (pintype "passive"))
      (node (ref "C40") (pin "2") (pinfunction "2_2") (pintype "passive"))
      (node (ref "C41") (pin "1") (pinfunction "1_1") (pintype "passive"))
      (node (ref "C42") (pin "2") (pinfunction "2_2") (pintype "passive"))
      (node (ref "C43") (pin "1") (pinfunction "1_1") (pintype "passive"))
      (node (ref "P10") (pin "97") (pinfunction "97_97") (pintype "passive"))
      (node (ref "P10") (pin "98") (pinfunction "98_98") (pintype "passive"))
      (node (ref "P10") (pin "A2") (pinfunction "A2_A2") (pintype "passive"))
      (node (ref "P10") (pin "A24") (pinfunction "A24_A24") (pintype "passive"))
      (node (ref "P10") (pin "A29") (pinfunction "A29_A29") (pintype "passive"))
      (node (ref "P10") (pin "A31") (pinfunction "A31_A31") (pintype "passive"))
      (node (ref "P10") (pin "B2") (pinfunction "B2_B2") (pintype "passive"))
      (node (ref "P10") (pin "B24") (pinfunction "B24_B24") (pintype "passive"))
      (node (ref "P10") (pin "B29") (pinfunction "B29_B29") (pintype "passive"))
      (node (ref "P10") (pin "B31") (pinfunction "B31_B31") (pintype "passive"))
      (node (ref "P10") (pin "C2") (pinfunction "C2_C2") (pintype "passive"))
      (node (ref "P10") (pin "C24") (pinfunction "C24_C24") (pintype "passive"))
      (node (ref "P10") (pin "C29") (pinfunction "C29_C29") (pintype "passive"))
      (node (ref "P10") (pin "C31") (pinfunction "C31_C31") (pintype "passive"))
      (node (ref "R13") (pin "1") (pinfunction "1_1") (pintype "passive"))
      (node (ref "R19") (pin "1") (pinfunction "1_1") (pintype "passive"))
      (node (ref "R25") (pin "1") (pinfunction "1_1") (pintype "passive"))
      (node (ref "R28") (pin "2") (pinfunction "2_2") (pintype "passive"))
      (node (ref "R54") (pin "2") (pinfunction "2_2") (pintype "passive"))
      (node (ref "U10") (pin "3") (pinfunction "A_3") (pintype "passive"))
      (node (ref "U11") (pin "2") (pinfunction "K_2") (pintype "passive"))
      (node (ref "U23") (pin "7") (pinfunction "GND_7") (pintype "power_in"))
      (node (ref "U8") (pin "2") (pinfunction "AVSS_2") (pintype "power_in"))
      (node (ref "U8") (pin "29") (pinfunction "AVSS_29") (pintype "power_in"))
      (node (ref "U8") (pin "31") (pinfunction "SENSE_31") (pintype "input"))
      (node (ref "U8") (pin "33") (pinfunction "REFCOM_33") (pintype "power_in"))
      (node (ref "U9") (pin "3") (pinfunction "IN+_3") (pintype "input"))
    )
    (net (code "96") (name "DGND") (class "Default")
      (node (ref "C38") (pin "1") (pinfunction "1_1") (pintype "passive"))
      (node (ref "C39") (pin "1") (pinfunction "1_1") (pintype "passive"))
      (node (ref "C44") (pin "2") (pinfunction "2_2") (pintype "passive"))
      (node (ref "C45") (pin "2") (pinfunction "2_2") (pintype "passive"))
      (node (ref "J2") (pin "1") (pinfunction "1_1") (pintype "passive"))
      (node (ref "R28") (pin "1") (pinfunction "1_1") (pintype "passive"))
      (node (ref "U12") (pin "1") (pinfunction "GND_1") (pintype "power_in"))
      (node (ref "U12") (pin "3") (pinfunction "NC_3") (pintype "passive"))
      (node (ref "U12") (pin "4") (pinfunction "NC_4") (pintype "passive"))
      (node (ref "U12") (pin "5") (pinfunction "NC_5") (pintype "passive"))
      (node (ref "U12") (pin "6") (pinfunction "NC_6") (pintype "passive"))
      (node (ref "U5") (pin "1") (pinfunction "~{OE}_1") (pintype "input"))
      (node (ref "U5") (pin "10") (pinfunction "GND_10") (pintype "power_in"))
      (node (ref "U6") (pin "1") (pinfunction "~{OE}_1") (pintype "input"))
      (node (ref "U6") (pin "10") (pinfunction "GND_10") (pintype "power_in"))
      (node (ref "U8") (pin "1") (pinfunction "DVSS_1") (pintype "power_in"))
      (node (ref "U8") (pin "5") (pinfunction "DRVSS_5") (pintype "power_in"))
      (node (ref "VR2") (pin "1") (pinfunction "GND_1") (pintype "passive"))
    )
    (net (code "97") (name "Net-(C34-Pad1)") (class "Default")
      (node (ref "C34") (pin "1") (pinfunction "1_1") (pintype "passive"))
      (node (ref "R23") (pin "2") (pinfunction "2_2") (pintype "passive"))
      (node (ref "R24") (pin "1") (pinfunction "1_1") (pintype "passive"))
    )
    (net (code "98") (name "Net-(D1-K)") (class "Default")
      (node (ref "C34") (pin "2") (pinfunction "2_2") (pintype "passive"))
      (node (ref "D1") (pin "3") (pinfunction "K_3") (pintype "passive"))
      (node (ref "R20") (pin "1") (pinfunction "1_1") (pintype "passive"))
      (node (ref "R25") (pin "2") (pinfunction "2_2") (pintype "passive"))
      (node (ref "U9") (pin "6") (pinfunction "IN-_6") (pintype "input"))
      (node (ref "U9") (pin "7") (pinfunction "OUT_7") (pintype "output"))
    )
    (net (code "99") (name "Net-(R18-Pad1)") (class "Default")
      (node (ref "R18") (pin "1") (pinfunction "1_1") (pintype "passive"))
      (node (ref "R19") (pin "2") (pinfunction "2_2") (pintype "passive"))
    )
    (net (code "100") (name "Net-(R21-+)") (class "Default")
      (node (ref "R21") (pin "CW") (pinfunction "+_CW") (pintype "passive"))
      (node (ref "R22") (pin "2") (pinfunction "2_2") (pintype "passive"))
      (node (ref "U9") (pin "2") (pinfunction "IN-_2") (pintype "input"))
    )
    (net (code "101") (name "Net-(R21--)") (class "Default")
      (node (ref "R21") (pin "CCW") (pinfunction "-_CCW") (pintype "passive"))
      (node (ref "R21") (pin "W") (pinfunction "W_W") (pintype "passive"))
      (node (ref "R23") (pin "1") (pinfunction "1_1") (pintype "passive"))
      (node (ref "U9") (pin "1") (pinfunction "OUT_1") (pintype "output"))
    )
    (net (code "102") (name "Net-(U7-+IN)") (class "Default")
      (node (ref "C25") (pin "1") (pinfunction "1_1") (pintype "passive"))
      (node (ref "R15") (pin "1") (pinfunction "1_1") (pintype "passive"))
      (node (ref "R20") (pin "2") (pinfunction "2_2") (pintype "passive"))
      (node (ref "U7") (pin "8") (pinfunction "+IN_8") (pintype "passive"))
    )
    (net (code "103") (name "Net-(U7--IN)") (class "Default")
      (node (ref "C24") (pin "1") (pinfunction "1_1") (pintype "passive"))
      (node (ref "R14") (pin "1") (pinfunction "1_1") (pintype "passive"))
      (node (ref "R18") (pin "2") (pinfunction "2_2") (pintype "passive"))
      (node (ref "U7") (pin "1") (pinfunction "-IN_1") (pintype "passive"))
    )
    (net (code "104") (name "Net-(U7-VCOM)") (class "Default")
      (node (ref "C28") (pin "2") (pinfunction "2_2") (pintype "passive"))
      (node (ref "U7") (pin "2") (pinfunction "VCOM_2") (pintype "passive"))
      (node (ref "U8") (pin "39") (pinfunction "CML_39") (pintype "power_in"))
    )
    (net (code "105") (name "Net-(U8-BIAS)") (class "Default")
      (node (ref "R13") (pin "2") (pinfunction "2_2") (pintype "passive"))
      (node (ref "U8") (pin "35") (pinfunction "BIAS_35") (pintype "passive"))
    )
    (net (code "106") (name "Net-(U8-CAPB)") (class "Default")
      (node (ref "C27") (pin "2") (pinfunction "2_2") (pintype "passive"))
      (node (ref "C29") (pin "1") (pinfunction "1_1") (pintype "passive"))
      (node (ref "C31") (pin "1") (pinfunction "1_1") (pintype "passive"))
      (node (ref "U8") (pin "36") (pinfunction "CAPB_36") (pintype "passive"))
    )
    (net (code "107") (name "Net-(U8-CAPT)") (class "Default")
      (node (ref "C26") (pin "1") (pinfunction "1_1") (pintype "passive"))
      (node (ref "C27") (pin "1") (pinfunction "1_1") (pintype "passive"))
      (node (ref "C29") (pin "2") (pinfunction "2_2") (pintype "passive"))
      (node (ref "U8") (pin "37") (pinfunction "CAPT_37") (pintype "passive"))
    )
    (net (code "108") (name "Net-(U8-VREF)") (class "Default")
      (node (ref "C32") (pin "1") (pinfunction "1_1") (pintype "passive"))
      (node (ref "C33") (pin "2") (pinfunction "2_2") (pintype "passive"))
      (node (ref "U8") (pin "32") (pinfunction "VREF_32") (pintype "bidirectional"))
    )
    (net (code "109") (name "Net-(U9B-IN+)") (class "Default")
      (node (ref "C35") (pin "2") (pinfunction "2_2") (pintype "passive"))
      (node (ref "R24") (pin "2") (pinfunction "2_2") (pintype "passive"))
      (node (ref "U9") (pin "5") (pinfunction "IN+_5") (pintype "input"))
    )
    (net (code "110") (name "Net-(U21-ADJ)") (class "Default")
      (node (ref "R54") (pin "1") (pinfunction "1_1") (pintype "passive"))
      (node (ref "R56") (pin "2") (pinfunction "2_2") (pintype "passive"))
      (node (ref "U21") (pin "1") (pinfunction "ADJ_1") (pintype "input"))
    )
    (net (code "111") (name "VCCO") (class "Default")
      (node (ref "C45") (pin "1") (pinfunction "1_1") (pintype "passive"))
      (node (ref "R29") (pin "2") (pinfunction "2_2") (pintype "passive"))
      (node (ref "U23") (pin "14") (pinfunction "VDD_14") (pintype "power_in"))
      (node (ref "U8") (pin "6") (pinfunction "DRVDD_6") (pintype "power_in"))
      (node (ref "VR2") (pin "2") (pinfunction "Vout_2") (pintype "passive"))
    )
    (net (code "112") (name "VE") (class "Default")
      (node (ref "P10") (pin "A32") (pinfunction "A32_A32") (pintype "passive"))
      (node (ref "P10") (pin "B32") (pinfunction "B32_B32") (pintype "passive"))
      (node (ref "P10") (pin "C32") (pinfunction "C32_C32") (pintype "passive"))
    )
    (net (code "113") (name "VO") (class "Default")
      (node (ref "R22") (pin "1") (pinfunction "1_1") (pintype "passive"))
    )
    (net (code "114") (name "unconnected-(P10-PadA16)") (class "Default")
      (node (ref "P10") (pin "A16") (pinfunction "A16_A16") (pintype "passive"))
    )
    (net (code "115") (name "unconnected-(P10-PadA17)") (class "Default")
      (node (ref "P10") (pin "A17") (pinfunction "A17_A17") (pintype "passive"))
    )
    (net (code "116") (name "unconnected-(P10-PadA20)") (class "Default")
      (node (ref "P10") (pin "A20") (pinfunction "A20_A20") (pintype "passive+no_connect"))
    )
    (net (code "117") (name "unconnected-(P10-PadA21)") (class "Default")
      (node (ref "P10") (pin "A21") (pinfunction "A21_A21") (pintype "passive+no_connect"))
    )
    (net (code "118") (name "unconnected-(P10-PadA22)") (class "Default")
      (node (ref "P10") (pin "A22") (pinfunction "A22_A22") (pintype "passive+no_connect"))
    )
    (net (code "119") (name "unconnected-(P10-PadA23)") (class "Default")
      (node (ref "P10") (pin "A23") (pinfunction "A23_A23") (pintype "passive"))
    )
    (net (code "120") (name "unconnected-(P10-PadA25)") (class "Default")
      (node (ref "P10") (pin "A25") (pinfunction "A25_A25") (pintype "passive+no_connect"))
    )
    (net (code "121") (name "unconnected-(P10-PadA26)") (class "Default")
      (node (ref "P10") (pin "A26") (pinfunction "A26_A26") (pintype "passive+no_connect"))
    )
    (net (code "122") (name "unconnected-(P10-PadA27)") (class "Default")
      (node (ref "P10") (pin "A27") (pinfunction "A27_A27") (pintype "passive+no_connect"))
    )
    (net (code "123") (name "unconnected-(P10-PadA28)") (class "Default")
      (node (ref "P10") (pin "A28") (pinfunction "A28_A28") (pintype "passive+no_connect"))
    )
    (net (code "124") (name "unconnected-(P10-PadB4)") (class "Default")
      (node (ref "P10") (pin "B4") (pinfunction "B4_B4") (pintype "passive+no_connect"))
    )
    (net (code "125") (name "unconnected-(P10-PadB5)") (class "Default")
      (node (ref "P10") (pin "B5") (pinfunction "B5_B5") (pintype "passive+no_connect"))
    )
    (net (code "126") (name "unconnected-(P10-PadB6)") (class "Default")
      (node (ref "P10") (pin "B6") (pinfunction "B6_B6") (pintype "passive+no_connect"))
    )
    (net (code "127") (name "unconnected-(P10-PadB7)") (class "Default")
      (node (ref "P10") (pin "B7") (pinfunction "B7_B7") (pintype "passive+no_connect"))
    )
    (net (code "128") (name "unconnected-(P10-PadB8)") (class "Default")
      (node (ref "P10") (pin "B8") (pinfunction "B8_B8") (pintype "passive+no_connect"))
    )
    (net (code "129") (name "unconnected-(P10-PadB9)") (class "Default")
      (node (ref "P10") (pin "B9") (pinfunction "B9_B9") (pintype "passive+no_connect"))
    )
    (net (code "130") (name "unconnected-(P10-PadB10)") (class "Default")
      (node (ref "P10") (pin "B10") (pinfunction "B10_B10") (pintype "passive+no_connect"))
    )
    (net (code "131") (name "unconnected-(P10-PadB11)") (class "Default")
      (node (ref "P10") (pin "B11") (pinfunction "B11_B11") (pintype "passive+no_connect"))
    )
    (net (code "132") (name "unconnected-(P10-PadB16)") (class "Default")
      (node (ref "P10") (pin "B16") (pinfunction "B16_B16") (pintype "passive"))
    )
    (net (code "133") (name "unconnected-(P10-PadB17)") (class "Default")
      (node (ref "P10") (pin "B17") (pinfunction "B17_B17") (pintype "passive"))
    )
    (net (code "134") (name "unconnected-(P10-PadB18)") (class "Default")
      (node (ref "P10") (pin "B18") (pinfunction "B18_B18") (pintype "passive"))
    )
    (net (code "135") (name "unconnected-(P10-PadB19)") (class "Default")
      (node (ref "P10") (pin "B19") (pinfunction "B19_B19") (pintype "passive"))
    )
    (net (code "136") (name "unconnected-(P10-PadB20)") (class "Default")
      (node (ref "P10") (pin "B20") (pinfunction "B20_B20") (pintype "passive"))
    )
    (net (code "137") (name "unconnected-(P10-PadB21)") (class "Default")
      (node (ref "P10") (pin "B21") (pinfunction "B21_B21") (pintype "passive"))
    )
    (net (code "138") (name "unconnected-(P10-PadB22)") (class "Default")
      (node (ref "P10") (pin "B22") (pinfunction "B22_B22") (pintype "passive"))
    )
    (net (code "139") (name "unconnected-(P10-PadB23)") (class "Default")
      (node (ref "P10") (pin "B23") (pinfunction "B23_B23") (pintype "passive"))
    )
    (net (code "140") (name "unconnected-(P10-PadB25)") (class "Default")
      (node (ref "P10") (pin "B25") (pinfunction "B25_B25") (pintype "passive+no_connect"))
    )
    (net (code "141") (name "unconnected-(P10-PadB26)") (class "Default")
      (node (ref "P10") (pin "B26") (pinfunction "B26_B26") (pintype "passive+no_connect"))
    )
    (net (code "142") (name "unconnected-(P10-PadB27)") (class "Default")
      (node (ref "P10") (pin "B27") (pinfunction "B27_B27") (pintype "passive+no_connect"))
    )
    (net (code "143") (name "unconnected-(P10-PadB28)") (class "Default")
      (node (ref "P10") (pin "B28") (pinfunction "B28_B28") (pintype "passive+no_connect"))
    )
    (net (code "144") (name "unconnected-(P10-PadC20)") (class "Default")
      (node (ref "P10") (pin "C20") (pinfunction "C20_C20") (pintype "passive+no_connect"))
    )
    (net (code "145") (name "unconnected-(P10-PadC21)") (class "Default")
      (node (ref "P10") (pin "C21") (pinfunction "C21_C21") (pintype "passive+no_connect"))
    )
    (net (code "146") (name "unconnected-(P10-PadC22)") (class "Default")
      (node (ref "P10") (pin "C22") (pinfunction "C22_C22") (pintype "passive+no_connect"))
    )
    (net (code "147") (name "unconnected-(P10-PadC23)") (class "Default")
      (node (ref "P10") (pin "C23") (pinfunction "C23_C23") (pintype "passive"))
    )
    (net (code "148") (name "unconnected-(P10-PadC25)") (class "Default")
      (node (ref "P10") (pin "C25") (pinfunction "C25_C25") (pintype "passive+no_connect"))
    )
    (net (code "149") (name "unconnected-(P10-PadC26)") (class "Default")
      (node (ref "P10") (pin "C26") (pinfunction "C26_C26") (pintype "passive+no_connect"))
    )
    (net (code "150") (name "unconnected-(P10-PadC27)") (class "Default")
      (node (ref "P10") (pin "C27") (pinfunction "C27_C27") (pintype "passive+no_connect"))
    )
    (net (code "151") (name "unconnected-(P10-PadC28)") (class "Default")
      (node (ref "P10") (pin "C28") (pinfunction "C28_C28") (pintype "passive+no_connect"))
    )
    (net (code "152") (name "unconnected-(U7-NC-Pad7)") (class "Default")
      (node (ref "U7") (pin "7") (pinfunction "NC_7") (pintype "passive"))
    )
    (net (code "153") (name "unconnected-(U8-NC-Pad8)") (class "Default")
      (node (ref "U8") (pin "8") (pinfunction "NC_8") (pintype "passive+no_connect"))
    )
    (net (code "154") (name "unconnected-(U8-NC-Pad9)") (class "Default")
      (node (ref "U8") (pin "9") (pinfunction "NC_9") (pintype "passive+no_connect"))
    )
    (net (code "155") (name "unconnected-(U8-NC-Pad10)") (class "Default")
      (node (ref "U8") (pin "10") (pinfunction "NC_10") (pintype "passive+no_connect"))
    )
    (net (code "156") (name "unconnected-(U8-NC-Pad26)") (class "Default")
      (node (ref "U8") (pin "26") (pinfunction "NC_26") (pintype "passive+no_connect"))
    )
    (net (code "157") (name "unconnected-(U8-NC-Pad27)") (class "Default")
      (node (ref "U8") (pin "27") (pinfunction "NC_27") (pintype "passive+no_connect"))
    )
    (net (code "158") (name "unconnected-(U8-NC-Pad30)") (class "Default")
      (node (ref "U8") (pin "30") (pinfunction "NC_30") (pintype "passive+no_connect"))
    )
    (net (code "159") (name "unconnected-(U8-NC-Pad34)") (class "Default")
      (node (ref "U8") (pin "34") (pinfunction "NC_34") (pintype "passive+no_connect"))
    )
    (net (code "160") (name "unconnected-(U8-NC-Pad38)") (class "Default")
      (node (ref "U8") (pin "38") (pinfunction "NC_38") (pintype "passive+no_connect"))
    )
    (net (code "161") (name "unconnected-(U8-NC-Pad40)") (class "Default")
      (node (ref "U8") (pin "40") (pinfunction "NC_40") (pintype "passive+no_connect"))
    )
    (net (code "162") (name "unconnected-(U8-NC-Pad43)") (class "Default")
      (node (ref "U8") (pin "43") (pinfunction "NC_43") (pintype "passive+no_connect"))
    )
    (net (code "163") (name "unconnected-(U8-NC-Pad44)") (class "Default")
      (node (ref "U8") (pin "44") (pinfunction "NC_44") (pintype "passive+no_connect"))
    )
    (net (code "164") (name "unconnected-(U10-R-Pad1)") (class "Default")
      (node (ref "U10") (pin "1") (pinfunction "R_1") (pintype "passive"))
    )
    (net (code "165") (name "unconnected-(U11-R-Pad1)") (class "Default")
      (node (ref "U11") (pin "1") (pinfunction "R_1") (pintype "passive"))
    )
    (net (code "166") (name "unconnected-(U23C-A-Pad5)") (class "Default")
      (node (ref "U23") (pin "5") (pinfunction "A_5") (pintype "input"))
    )
    (net (code "167") (name "unconnected-(U23C-Y-Pad6)") (class "Default")
      (node (ref "U23") (pin "6") (pinfunction "Y_6") (pintype "output"))
    )
    (net (code "168") (name "unconnected-(U23D-A-Pad9)") (class "Default")
      (node (ref "U23") (pin "9") (pinfunction "A_9") (pintype "input"))
    )
    (net (code "169") (name "unconnected-(U23D-Y-Pad8)") (class "Default")
      (node (ref "U23") (pin "8") (pinfunction "Y_8") (pintype "output"))
    )
    (net (code "170") (name "unconnected-(U23E-A-Pad11)") (class "Default")
      (node (ref "U23") (pin "11") (pinfunction "A_11") (pintype "input"))
    )
    (net (code "171") (name "unconnected-(U23E-Y-Pad10)") (class "Default")
      (node (ref "U23") (pin "10") (pinfunction "Y_10") (pintype "output"))
    )
    (net (code "172") (name "unconnected-(U23F-A-Pad13)") (class "Default")
      (node (ref "U23") (pin "13") (pinfunction "A_13") (pintype "input"))
    )
    (net (code "173") (name "unconnected-(U23F-Y-Pad12)") (class "Default")
      (node (ref "U23") (pin "12") (pinfunction "Y_12") (pintype "output"))
    )
  )
)
